# digit.net
KiCad netlist of a schematic drawn in Altium Designer
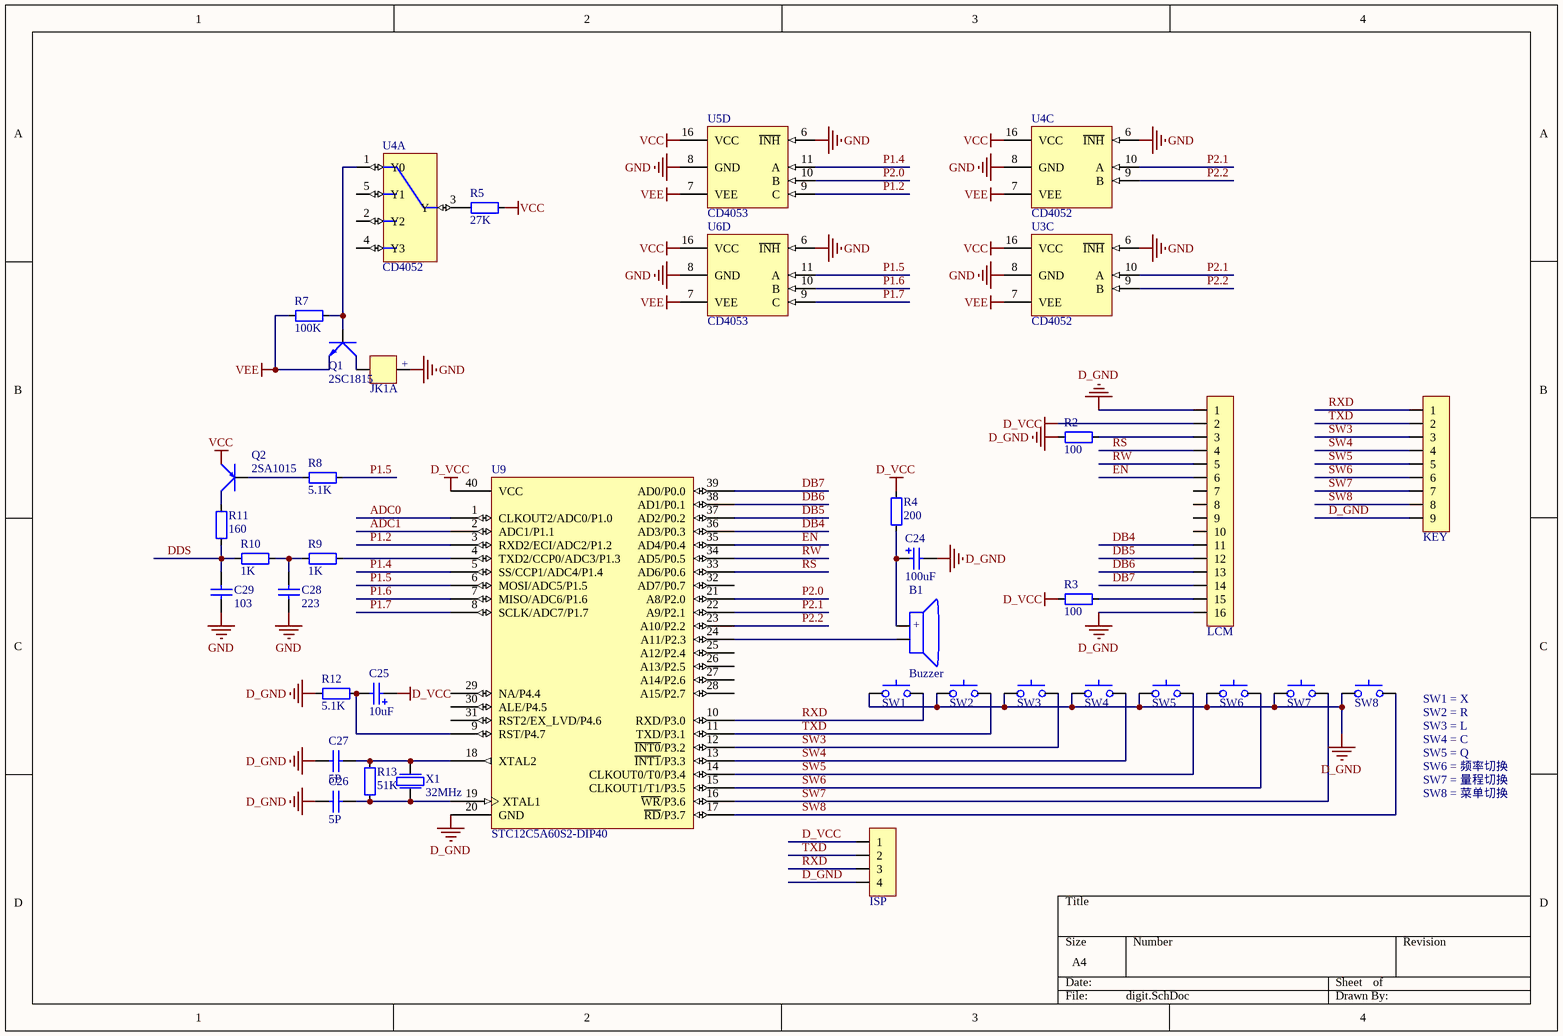
[diagram p0: digit.SchDoc]

(export (version "E")
  (design (tool "Eeschema 10.0.6"))
  (components
    (comp (ref "B1")
      (value "Buzzer")
      (footprint "Buzzer_1")
      (description "蜂鸣器")
      (libsource (lib "Eblis") (part "Buzzer"))
    )
    (comp (ref "C24")
      (value "100uF")
      (footprint "CR3")
      (description "插脚有极电容")
      (fields (field (name "Comment") "CAP POL"))
      (libsource (lib "Eblis") (part "CAP POL"))
    )
    (comp (ref "C25")
      (value "10uF")
      (footprint "CR2")
      (description "插脚有极电容")
      (fields (field (name "Comment") "CAP POL"))
      (libsource (lib "Eblis") (part "CAP POL"))
    )
    (comp (ref "C26")
      (value "5P")
      (footprint "C0805")
      (description "贴片无极电容")
      (fields (field (name "Comment") "CAP_SMD"))
      (libsource (lib "Eblis") (part "CAP_SMD"))
    )
    (comp (ref "C27")
      (value "5P")
      (footprint "C0805")
      (description "贴片无极电容")
      (fields (field (name "Comment") "CAP_SMD"))
      (libsource (lib "Eblis") (part "CAP_SMD"))
    )
    (comp (ref "C28")
      (value "223")
      (footprint "CL0704")
      (description "插脚无极电容")
      (fields (field (name "Comment") "CAP"))
      (libsource (lib "Eblis") (part "CAP"))
    )
    (comp (ref "C29")
      (value "103")
      (footprint "CL0704")
      (description "插脚无极电容")
      (fields (field (name "Comment") "CAP"))
      (libsource (lib "Eblis") (part "CAP"))
    )
    (comp (ref "ISP") (value "Socket P4") (footprint "SPH254-4") (libsource (lib "Eblis") (part "Socket P4")))
    (comp (ref "JK1")
      (value "JK-2")
      (footprint "JK-G6S2")
      (description "小型双刀双掷继电器")
      (libsource (lib "Eblis") (part "JK-2"))
    )
    (comp (ref "KEY") (value "Socket P9") (footprint "XH254-9") (libsource (lib "Eblis") (part "Socket P9")))
    (comp (ref "LCM")
      (value "Socket P16")
      (footprint "XH254-16")
      (libsource (lib "Eblis") (part "Socket P16"))
    )
    (comp (ref "Q1")
      (value "2SC1815")
      (footprint "TO-92")
      (description "低压小功率NPN管(0,15A/50V/0.4W)")
      (libsource (lib "Eblis") (part "2SC1815"))
    )
    (comp (ref "Q2")
      (value "2SA1015")
      (footprint "TO-92")
      (description "低压小功率PNP管(0.15A/50V/0.4W)")
      (libsource (lib "Eblis") (part "2SA1015"))
    )
    (comp (ref "R2")
      (value "100")
      (footprint "R0603")
      (description "贴片电阻")
      (fields (field (name "Comment") "RES_SMD"))
      (libsource (lib "Eblis") (part "RES_SMD"))
    )
    (comp (ref "R3")
      (value "100")
      (footprint "R0603")
      (description "贴片电阻")
      (fields (field (name "Comment") "RES_SMD"))
      (libsource (lib "Eblis") (part "RES_SMD"))
    )
    (comp (ref "R4")
      (value "200")
      (footprint "R0805")
      (description "贴片电阻")
      (fields (field (name "Comment") "RES_SMD"))
      (libsource (lib "Eblis") (part "RES_SMD"))
    )
    (comp (ref "R5")
      (value "27K")
      (footprint "R0805")
      (description "贴片电阻")
      (fields (field (name "Comment") "RES_SMD"))
      (libsource (lib "Eblis") (part "RES_SMD"))
    )
    (comp (ref "R7")
      (value "100K")
      (footprint "R0805")
      (description "贴片电阻")
      (fields (field (name "Comment") "RES_SMD"))
      (libsource (lib "Eblis") (part "RES_SMD"))
    )
    (comp (ref "R8")
      (value "5.1K")
      (footprint "R0805")
      (description "贴片电阻")
      (fields (field (name "Comment") "RES_SMD"))
      (libsource (lib "Eblis") (part "RES_SMD"))
    )
    (comp (ref "R9")
      (value "1K")
      (footprint "AXIAL-0.3")
      (description "插脚电阻")
      (fields (field (name "Comment") "RES"))
      (libsource (lib "Eblis") (part "RES"))
    )
    (comp (ref "R10")
      (value "1K")
      (footprint "AXIAL-0.3")
      (description "插脚电阻")
      (fields (field (name "Comment") "RES"))
      (libsource (lib "Eblis") (part "RES"))
    )
    (comp (ref "R11")
      (value "160")
      (footprint "AXIAL-0.3")
      (description "插脚电阻")
      (fields (field (name "Comment") "RES"))
      (libsource (lib "Eblis") (part "RES"))
    )
    (comp (ref "R12")
      (value "5.1K")
      (footprint "R0805")
      (description "贴片电阻")
      (fields (field (name "Comment") "RES_SMD"))
      (libsource (lib "Eblis") (part "RES_SMD"))
    )
    (comp (ref "R13")
      (value "51K")
      (footprint "R0805")
      (description "贴片电阻")
      (fields (field (name "Comment") "RES_SMD"))
      (libsource (lib "Eblis") (part "RES_SMD"))
    )
    (comp (ref "SW1")
      (value "SW")
      (footprint "SW0606")
      (description "小型按键开关")
      (libsource (lib "Eblis") (part "SW"))
    )
    (comp (ref "SW2")
      (value "SW")
      (footprint "SW0606")
      (description "小型按键开关")
      (libsource (lib "Eblis") (part "SW"))
    )
    (comp (ref "SW3")
      (value "SW")
      (footprint "SW0606")
      (description "小型按键开关")
      (libsource (lib "Eblis") (part "SW"))
    )
    (comp (ref "SW4")
      (value "SW")
      (footprint "SW0606")
      (description "小型按键开关")
      (libsource (lib "Eblis") (part "SW"))
    )
    (comp (ref "SW5")
      (value "SW")
      (footprint "SW0606")
      (description "小型按键开关")
      (libsource (lib "Eblis") (part "SW"))
    )
    (comp (ref "SW6")
      (value "SW")
      (footprint "SW0606")
      (description "小型按键开关")
      (libsource (lib "Eblis") (part "SW"))
    )
    (comp (ref "SW7")
      (value "SW")
      (footprint "SW0606")
      (description "小型按键开关")
      (libsource (lib "Eblis") (part "SW"))
    )
    (comp (ref "SW8")
      (value "SW")
      (footprint "SW0606")
      (description "小型按键开关")
      (libsource (lib "Eblis") (part "SW"))
    )
    (comp (ref "U3") (value "CD4052") (footprint "DIP16") (libsource (lib "Eblis") (part "CD4052")))
    (comp (ref "U4") (value "CD4052") (footprint "DIP16") (libsource (lib "Eblis") (part "CD4052")))
    (comp (ref "U5") (value "CD4053") (footprint "DIP16") (libsource (lib "Eblis") (part "CD4053")))
    (comp (ref "U6") (value "CD4053") (footprint "SOP16") (libsource (lib "Eblis") (part "CD4053")))
    (comp (ref "U9")
      (value "STC12C5A60S2-DIP40")
      (footprint "DIP40")
      (libsource (lib "Eblis") (part "STC12C5A60S2-DIP40"))
    )
    (comp (ref "X1")
      (value "32MHz")
      (footprint "XTAL-HC49US")
      (description "无源晶振")
      (fields (field (name "Comment") "XTAL"))
      (libsource (lib "Eblis") (part "XTAL"))
    )
  )
  (nets
    (net (code "1") (name "/ADC0") (class "Default")
      (node (ref "U9") (pin "1") (pinfunction "CLKOUT2/ADC0/P1.0_1") (pintype "bidirectional"))
    )
    (net (code "2") (name "/ADC1") (class "Default")
      (node (ref "U9") (pin "2") (pinfunction "ADC1/P1.1_2") (pintype "bidirectional"))
    )
    (net (code "3") (name "/DB4") (class "Default")
      (node (ref "LCM") (pin "11") (pinfunction "11_11") (pintype "passive"))
      (node (ref "U9") (pin "36") (pinfunction "AD3/P0.3_36") (pintype "bidirectional"))
    )
    (net (code "4") (name "/DB5") (class "Default")
      (node (ref "LCM") (pin "12") (pinfunction "12_12") (pintype "passive"))
      (node (ref "U9") (pin "37") (pinfunction "AD2/P0.2_37") (pintype "bidirectional"))
    )
    (net (code "5") (name "/DB6") (class "Default")
      (node (ref "LCM") (pin "13") (pinfunction "13_13") (pintype "passive"))
      (node (ref "U9") (pin "38") (pinfunction "AD1/P0.1_38") (pintype "bidirectional"))
    )
    (net (code "6") (name "/DB7") (class "Default")
      (node (ref "LCM") (pin "14") (pinfunction "14_14") (pintype "passive"))
      (node (ref "U9") (pin "39") (pinfunction "AD0/P0.0_39") (pintype "bidirectional"))
    )
    (net (code "7") (name "/DDS") (class "Default")
      (node (ref "C29") (pin "2") (pinfunction "2_2") (pintype "passive"))
      (node (ref "R10") (pin "1") (pinfunction "1_1") (pintype "passive"))
      (node (ref "R11") (pin "1") (pinfunction "1_1") (pintype "passive"))
    )
    (net (code "8") (name "/EN") (class "Default")
      (node (ref "LCM") (pin "6") (pinfunction "6_6") (pintype "passive"))
      (node (ref "U9") (pin "35") (pinfunction "AD4/P0.4_35") (pintype "bidirectional"))
    )
    (net (code "9") (name "/P1.2") (class "Default")
      (node (ref "U5") (pin "9") (pinfunction "C_9") (pintype "input"))
      (node (ref "U9") (pin "3") (pinfunction "RXD2/ECI/ADC2/P1.2_3") (pintype "bidirectional"))
    )
    (net (code "10") (name "/P1.4") (class "Default")
      (node (ref "U5") (pin "11") (pinfunction "A_11") (pintype "input"))
      (node (ref "U9") (pin "5") (pinfunction "SS/CCP1/ADC4/P1.4_5") (pintype "bidirectional"))
    )
    (net (code "11") (name "/P1.5") (class "Default")
      (node (ref "R8") (pin "2") (pinfunction "2_2") (pintype "passive"))
      (node (ref "U6") (pin "11") (pinfunction "A_11") (pintype "input"))
      (node (ref "U9") (pin "6") (pinfunction "MOSI/ADC5/P1.5_6") (pintype "bidirectional"))
    )
    (net (code "12") (name "/P1.6") (class "Default")
      (node (ref "U6") (pin "10") (pinfunction "B_10") (pintype "input"))
      (node (ref "U9") (pin "7") (pinfunction "MISO/ADC6/P1.6_7") (pintype "bidirectional"))
    )
    (net (code "13") (name "/P1.7") (class "Default")
      (node (ref "U6") (pin "9") (pinfunction "C_9") (pintype "input"))
      (node (ref "U9") (pin "8") (pinfunction "SCLK/ADC7/P1.7_8") (pintype "bidirectional"))
    )
    (net (code "14") (name "/P2.0") (class "Default")
      (node (ref "U5") (pin "10") (pinfunction "B_10") (pintype "input"))
      (node (ref "U9") (pin "21") (pinfunction "A8/P2.0_21") (pintype "bidirectional"))
    )
    (net (code "15") (name "/P2.1") (class "Default")
      (node (ref "U3") (pin "10") (pinfunction "A_10") (pintype "input"))
      (node (ref "U4") (pin "10") (pinfunction "A_10") (pintype "input"))
      (node (ref "U9") (pin "22") (pinfunction "A9/P2.1_22") (pintype "bidirectional"))
    )
    (net (code "16") (name "/P2.2") (class "Default")
      (node (ref "U3") (pin "9") (pinfunction "B_9") (pintype "input"))
      (node (ref "U4") (pin "9") (pinfunction "B_9") (pintype "input"))
      (node (ref "U9") (pin "23") (pinfunction "A10/P2.2_23") (pintype "bidirectional"))
    )
    (net (code "17") (name "/RS") (class "Default")
      (node (ref "LCM") (pin "4") (pinfunction "4_4") (pintype "passive"))
      (node (ref "U9") (pin "33") (pinfunction "AD6/P0.6_33") (pintype "bidirectional"))
    )
    (net (code "18") (name "/RW") (class "Default")
      (node (ref "LCM") (pin "5") (pinfunction "5_5") (pintype "passive"))
      (node (ref "U9") (pin "34") (pinfunction "AD5/P0.5_34") (pintype "bidirectional"))
    )
    (net (code "19") (name "/RXD") (class "Default")
      (node (ref "ISP") (pin "3") (pinfunction "3_3") (pintype "passive"))
      (node (ref "KEY") (pin "1") (pinfunction "1_1") (pintype "passive"))
      (node (ref "SW1") (pin "2") (pinfunction "2_2") (pintype "passive"))
      (node (ref "U9") (pin "10") (pinfunction "RXD/P3.0_10") (pintype "bidirectional"))
    )
    (net (code "20") (name "/SW3") (class "Default")
      (node (ref "KEY") (pin "3") (pinfunction "3_3") (pintype "passive"))
      (node (ref "SW3") (pin "2") (pinfunction "2_2") (pintype "passive"))
      (node (ref "U9") (pin "12") (pinfunction "~{INT0}/P3.2_12") (pintype "bidirectional"))
    )
    (net (code "21") (name "/SW4") (class "Default")
      (node (ref "KEY") (pin "4") (pinfunction "4_4") (pintype "passive"))
      (node (ref "SW4") (pin "2") (pinfunction "2_2") (pintype "passive"))
      (node (ref "U9") (pin "13") (pinfunction "~{INT1}/P3.3_13") (pintype "bidirectional"))
    )
    (net (code "22") (name "/SW5") (class "Default")
      (node (ref "KEY") (pin "5") (pinfunction "5_5") (pintype "passive"))
      (node (ref "SW5") (pin "2") (pinfunction "2_2") (pintype "passive"))
      (node (ref "U9") (pin "14") (pinfunction "CLKOUT0/T0/P3.4_14") (pintype "bidirectional"))
    )
    (net (code "23") (name "/SW6") (class "Default")
      (node (ref "KEY") (pin "6") (pinfunction "6_6") (pintype "passive"))
      (node (ref "SW6") (pin "2") (pinfunction "2_2") (pintype "passive"))
      (node (ref "U9") (pin "15") (pinfunction "CLKOUT1/T1/P3.5_15") (pintype "bidirectional"))
    )
    (net (code "24") (name "/SW7") (class "Default")
      (node (ref "KEY") (pin "7") (pinfunction "7_7") (pintype "passive"))
      (node (ref "SW7") (pin "2") (pinfunction "2_2") (pintype "passive"))
      (node (ref "U9") (pin "16") (pinfunction "~{WR}/P3.6_16") (pintype "bidirectional"))
    )
    (net (code "25") (name "/SW8") (class "Default")
      (node (ref "KEY") (pin "8") (pinfunction "8_8") (pintype "passive"))
      (node (ref "SW8") (pin "2") (pinfunction "2_2") (pintype "passive"))
      (node (ref "U9") (pin "17") (pinfunction "~{RD}/P3.7_17") (pintype "bidirectional"))
    )
    (net (code "26") (name "/TXD") (class "Default")
      (node (ref "ISP") (pin "2") (pinfunction "2_2") (pintype "passive"))
      (node (ref "KEY") (pin "2") (pinfunction "2_2") (pintype "passive"))
      (node (ref "SW2") (pin "2") (pinfunction "2_2") (pintype "passive"))
      (node (ref "U9") (pin "11") (pinfunction "TXD/P3.1_11") (pintype "bidirectional"))
    )
    (net (code "27") (name "D_GND") (class "Default")
      (node (ref "C24") (pin "2") (pinfunction "2_2") (pintype "passive"))
      (node (ref "C26") (pin "1") (pinfunction "1_1") (pintype "passive"))
      (node (ref "C27") (pin "1") (pinfunction "1_1") (pintype "passive"))
      (node (ref "ISP") (pin "4") (pinfunction "4_4") (pintype "passive"))
      (node (ref "KEY") (pin "9") (pinfunction "9_9") (pintype "passive"))
      (node (ref "LCM") (pin "1") (pinfunction "1_1") (pintype "passive"))
      (node (ref "LCM") (pin "16") (pinfunction "16_16") (pintype "passive"))
      (node (ref "R12") (pin "1") (pinfunction "1_1") (pintype "passive"))
      (node (ref "R2") (pin "2") (pinfunction "2_2") (pintype "passive"))
      (node (ref "SW1") (pin "1") (pinfunction "1_1") (pintype "passive"))
      (node (ref "SW2") (pin "1") (pinfunction "1_1") (pintype "passive"))
      (node (ref "SW3") (pin "1") (pinfunction "1_1") (pintype "passive"))
      (node (ref "SW4") (pin "1") (pinfunction "1_1") (pintype "passive"))
      (node (ref "SW5") (pin "1") (pinfunction "1_1") (pintype "passive"))
      (node (ref "SW6") (pin "1") (pinfunction "1_1") (pintype "passive"))
      (node (ref "SW7") (pin "1") (pinfunction "1_1") (pintype "passive"))
      (node (ref "SW8") (pin "1") (pinfunction "1_1") (pintype "passive"))
      (node (ref "U9") (pin "20") (pinfunction "GND_20") (pintype "power_in"))
    )
    (net (code "28") (name "D_VCC") (class "Default")
      (node (ref "C25") (pin "1") (pinfunction "1_1") (pintype "passive"))
      (node (ref "ISP") (pin "1") (pinfunction "1_1") (pintype "passive"))
      (node (ref "LCM") (pin "2") (pinfunction "2_2") (pintype "passive"))
      (node (ref "R3") (pin "2") (pinfunction "2_2") (pintype "passive"))
      (node (ref "R4") (pin "2") (pinfunction "2_2") (pintype "passive"))
      (node (ref "U9") (pin "40") (pinfunction "VCC_40") (pintype "power_in"))
    )
    (net (code "29") (name "GND") (class "Default")
      (node (ref "C28") (pin "1") (pinfunction "1_1") (pintype "passive"))
      (node (ref "C29") (pin "1") (pinfunction "1_1") (pintype "passive"))
      (node (ref "JK1") (pin "1") (pinfunction "1_1") (pintype "passive"))
      (node (ref "U3") (pin "6") (pinfunction "~{INH}_6") (pintype "input"))
      (node (ref "U3") (pin "8") (pinfunction "GND_8") (pintype "power_in"))
      (node (ref "U4") (pin "6") (pinfunction "~{INH}_6") (pintype "input"))
      (node (ref "U4") (pin "8") (pinfunction "GND_8") (pintype "power_in"))
      (node (ref "U5") (pin "6") (pinfunction "~{INH}_6") (pintype "input"))
      (node (ref "U5") (pin "8") (pinfunction "GND_8") (pintype "power_in"))
      (node (ref "U6") (pin "6") (pinfunction "~{INH}_6") (pintype "input"))
      (node (ref "U6") (pin "8") (pinfunction "GND_8") (pintype "power_in"))
    )
    (net (code "30") (name "Net-(B1-Pad1)") (class "Default")
      (node (ref "B1") (pin "1") (pinfunction "1_1") (pintype "passive"))
      (node (ref "C24") (pin "1") (pinfunction "1_1") (pintype "passive"))
      (node (ref "R4") (pin "1") (pinfunction "1_1") (pintype "passive"))
    )
    (net (code "31") (name "Net-(C28-Pad2)") (class "Default")
      (node (ref "C28") (pin "2") (pinfunction "2_2") (pintype "passive"))
      (node (ref "R10") (pin "2") (pinfunction "2_2") (pintype "passive"))
      (node (ref "R9") (pin "1") (pinfunction "1_1") (pintype "passive"))
    )
    (net (code "32") (name "Net-(JK1-Pad8)") (class "Default")
      (node (ref "JK1") (pin "8") (pinfunction "8_8") (pintype "passive"))
      (node (ref "Q1") (pin "2") (pinfunction "2_2") (pintype "passive"))
    )
    (net (code "33") (name "Net-(LCM-Pad3)") (class "Default")
      (node (ref "LCM") (pin "3") (pinfunction "3_3") (pintype "passive"))
      (node (ref "R2") (pin "1") (pinfunction "1_1") (pintype "passive"))
    )
    (net (code "34") (name "Net-(LCM-Pad15)") (class "Default")
      (node (ref "LCM") (pin "15") (pinfunction "15_15") (pintype "passive"))
      (node (ref "R3") (pin "1") (pinfunction "1_1") (pintype "passive"))
    )
    (net (code "35") (name "Net-(Q2-Pad1)") (class "Default")
      (node (ref "Q2") (pin "1") (pinfunction "1_1") (pintype "passive"))
      (node (ref "R8") (pin "1") (pinfunction "1_1") (pintype "passive"))
    )
    (net (code "36") (name "Net-(Q2-Pad2)") (class "Default")
      (node (ref "Q2") (pin "2") (pinfunction "2_2") (pintype "passive"))
      (node (ref "R11") (pin "2") (pinfunction "2_2") (pintype "passive"))
    )
    (net (code "37") (name "Net-(U4A-Y)") (class "Default")
      (node (ref "R5") (pin "1") (pinfunction "1_1") (pintype "passive"))
      (node (ref "U4") (pin "3") (pinfunction "Y_3") (pintype "bidirectional"))
    )
    (net (code "38") (name "Net-(U4A-Y0)") (class "Default")
      (node (ref "Q1") (pin "1") (pinfunction "1_1") (pintype "passive"))
      (node (ref "R7") (pin "2") (pinfunction "2_2") (pintype "passive"))
      (node (ref "U4") (pin "1") (pinfunction "Y0_1") (pintype "bidirectional"))
    )
    (net (code "39") (name "Net-(U9-A11{slash}P2.3)") (class "Default")
      (node (ref "B1") (pin "2") (pinfunction "2_2") (pintype "passive"))
      (node (ref "U9") (pin "24") (pinfunction "A11/P2.3_24") (pintype "bidirectional"))
    )
    (net (code "40") (name "Net-(U9-RST{slash}P4.7)") (class "Default")
      (node (ref "C25") (pin "2") (pinfunction "2_2") (pintype "passive"))
      (node (ref "R12") (pin "2") (pinfunction "2_2") (pintype "passive"))
      (node (ref "U9") (pin "9") (pinfunction "RST/P4.7_9") (pintype "bidirectional"))
    )
    (net (code "41") (name "Net-(U9-TXD2{slash}CCP0{slash}ADC3{slash}P1.3)") (class "Default")
      (node (ref "R9") (pin "2") (pinfunction "2_2") (pintype "passive"))
      (node (ref "U9") (pin "4") (pinfunction "TXD2/CCP0/ADC3/P1.3_4") (pintype "bidirectional"))
    )
    (net (code "42") (name "Net-(U9-XTAL1)") (class "Default")
      (node (ref "C26") (pin "2") (pinfunction "2_2") (pintype "passive"))
      (node (ref "R13") (pin "1") (pinfunction "1_1") (pintype "passive"))
      (node (ref "U9") (pin "19") (pinfunction "XTAL1_19") (pintype "input"))
      (node (ref "X1") (pin "1") (pinfunction "1_1") (pintype "passive"))
    )
    (net (code "43") (name "Net-(U9-XTAL2)") (class "Default")
      (node (ref "C27") (pin "2") (pinfunction "2_2") (pintype "passive"))
      (node (ref "R13") (pin "2") (pinfunction "2_2") (pintype "passive"))
      (node (ref "U9") (pin "18") (pinfunction "XTAL2_18") (pintype "output"))
      (node (ref "X1") (pin "3") (pinfunction "3_3") (pintype "passive"))
    )
    (net (code "44") (name "VCC") (class "Default")
      (node (ref "Q2") (pin "3") (pinfunction "3_3") (pintype "passive"))
      (node (ref "R5") (pin "2") (pinfunction "2_2") (pintype "passive"))
      (node (ref "U3") (pin "16") (pinfunction "VCC_16") (pintype "power_in"))
      (node (ref "U4") (pin "16") (pinfunction "VCC_16") (pintype "power_in"))
      (node (ref "U5") (pin "16") (pinfunction "VCC_16") (pintype "power_in"))
      (node (ref "U6") (pin "16") (pinfunction "VCC_16") (pintype "power_in"))
    )
    (net (code "45") (name "VEE") (class "Default")
      (node (ref "Q1") (pin "3") (pinfunction "3_3") (pintype "passive"))
      (node (ref "R7") (pin "1") (pinfunction "1_1") (pintype "passive"))
      (node (ref "U3") (pin "7") (pinfunction "VEE_7") (pintype "power_in"))
      (node (ref "U4") (pin "7") (pinfunction "VEE_7") (pintype "power_in"))
      (node (ref "U5") (pin "7") (pinfunction "VEE_7") (pintype "power_in"))
      (node (ref "U6") (pin "7") (pinfunction "VEE_7") (pintype "power_in"))
    )
    (net (code "46") (name "unconnected-(LCM-Pad7)") (class "Default")
      (node (ref "LCM") (pin "7") (pinfunction "7_7") (pintype "passive"))
    )
    (net (code "47") (name "unconnected-(LCM-Pad8)") (class "Default")
      (node (ref "LCM") (pin "8") (pinfunction "8_8") (pintype "passive"))
    )
    (net (code "48") (name "unconnected-(LCM-Pad9)") (class "Default")
      (node (ref "LCM") (pin "9") (pinfunction "9_9") (pintype "passive"))
    )
    (net (code "49") (name "unconnected-(LCM-Pad10)") (class "Default")
      (node (ref "LCM") (pin "10") (pinfunction "10_10") (pintype "passive"))
    )
    (net (code "50") (name "unconnected-(U4A-Y1-Pad5)") (class "Default")
      (node (ref "U4") (pin "5") (pinfunction "Y1_5") (pintype "bidirectional"))
    )
    (net (code "51") (name "unconnected-(U4A-Y2-Pad2)") (class "Default")
      (node (ref "U4") (pin "2") (pinfunction "Y2_2") (pintype "bidirectional"))
    )
    (net (code "52") (name "unconnected-(U4A-Y3-Pad4)") (class "Default")
      (node (ref "U4") (pin "4") (pinfunction "Y3_4") (pintype "bidirectional"))
    )
    (net (code "53") (name "unconnected-(U9-A12{slash}P2.4-Pad25)") (class "Default")
      (node (ref "U9") (pin "25") (pinfunction "A12/P2.4_25") (pintype "bidirectional"))
    )
    (net (code "54") (name "unconnected-(U9-A13{slash}P2.5-Pad26)") (class "Default")
      (node (ref "U9") (pin "26") (pinfunction "A13/P2.5_26") (pintype "bidirectional"))
    )
    (net (code "55") (name "unconnected-(U9-A14{slash}P2.6-Pad27)") (class "Default")
      (node (ref "U9") (pin "27") (pinfunction "A14/P2.6_27") (pintype "bidirectional"))
    )
    (net (code "56") (name "unconnected-(U9-A15{slash}P2.7-Pad28)") (class "Default")
      (node (ref "U9") (pin "28") (pinfunction "A15/P2.7_28") (pintype "bidirectional"))
    )
    (net (code "57") (name "unconnected-(U9-AD7{slash}P0.7-Pad32)") (class "Default")
      (node (ref "U9") (pin "32") (pinfunction "AD7/P0.7_32") (pintype "bidirectional"))
    )
    (net (code "58") (name "unconnected-(U9-ALE{slash}P4.5-Pad30)") (class "Default")
      (node (ref "U9") (pin "30") (pinfunction "ALE/P4.5_30") (pintype "bidirectional"))
    )
    (net (code "59") (name "unconnected-(U9-NA{slash}P4.4-Pad29)") (class "Default")
      (node (ref "U9") (pin "29") (pinfunction "NA/P4.4_29") (pintype "bidirectional"))
    )
    (net (code "60") (name "unconnected-(U9-RST2{slash}EX_LVD{slash}P4.6-Pad31)") (class "Default")
      (node (ref "U9") (pin "31") (pinfunction "RST2/EX_LVD/P4.6_31") (pintype "bidirectional"))
    )
  )
)
